# tinyduino-driver.net
KiCad netlist of a schematic drawn in EAGLE
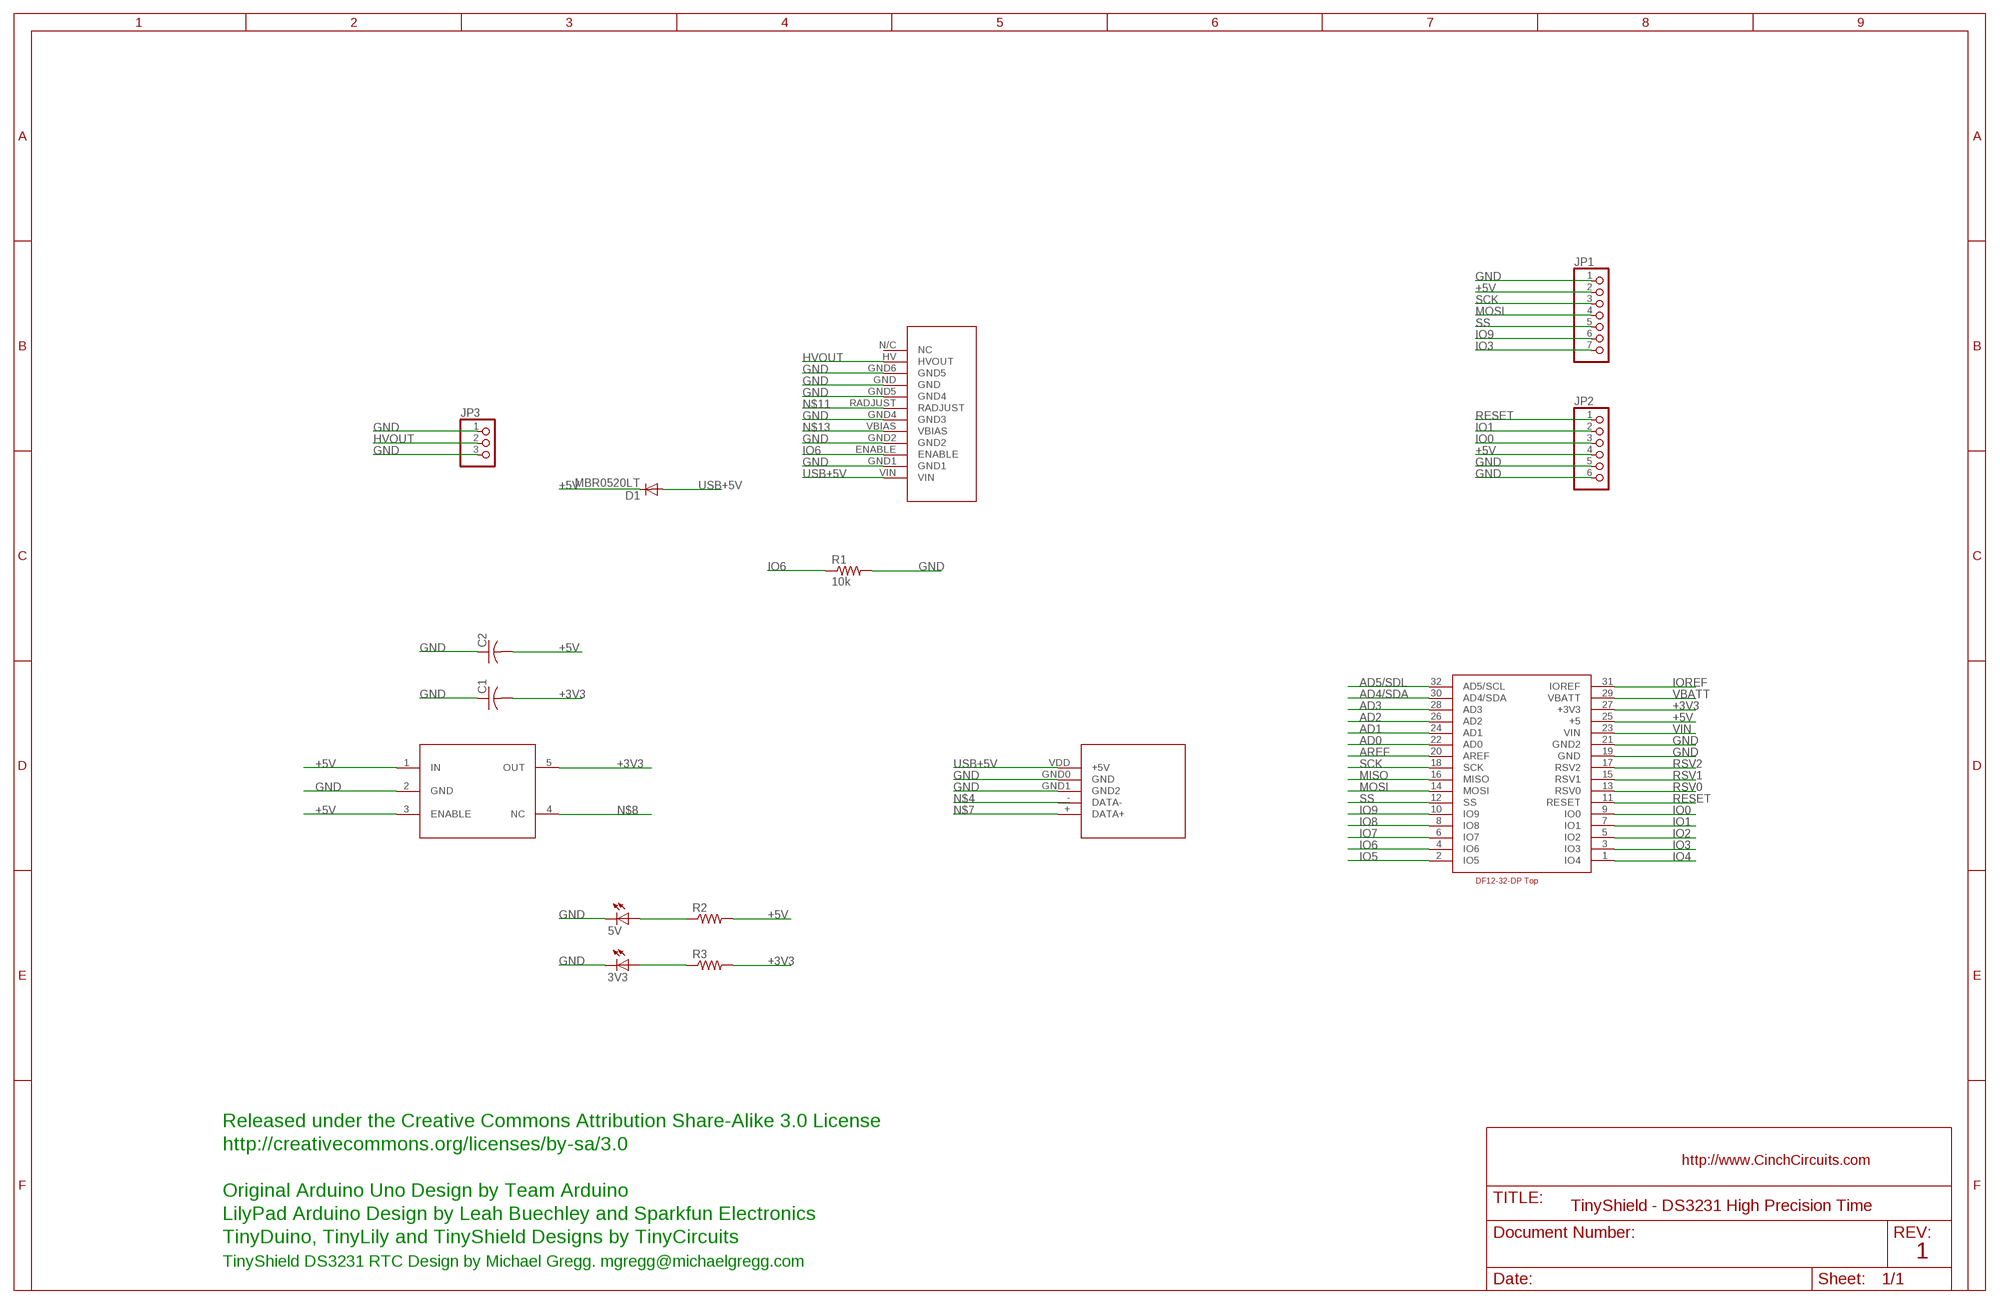
[diagram p0: schematic, sheet 1]

(export (version "E")
  (design (tool "Eeschema 10.0.6"))
  (components
    (comp (ref "3V3")
      (value "LEDCHIPLED_0603")
      (footprint "eagle-import:CHIPLED_0603")
      (libsource (lib "eagle-import") (part "LEDCHIPLED_0603"))
    )
    (comp (ref "5V")
      (value "LEDCHIPLED_0603")
      (footprint "eagle-import:CHIPLED_0603")
      (libsource (lib "eagle-import") (part "LEDCHIPLED_0603"))
    )
    (comp (ref "C1")
      (value "C-USC0805")
      (footprint "eagle-import:C0805")
      (libsource (lib "eagle-import") (part "C-USC0805"))
    )
    (comp (ref "C2")
      (value "C-USC0805")
      (footprint "eagle-import:C0805")
      (libsource (lib "eagle-import") (part "C-USC0805"))
    )
    (comp (ref "D1")
      (value "MBR0520LT")
      (footprint "eagle-import:SOD123")
      (libsource (lib "eagle-import") (part "MBR0520LT"))
    )
    (comp (ref "JP1")
      (value "PINHD-1X7")
      (footprint "eagle-import:1X07")
      (libsource (lib "eagle-import") (part "PINHD-1X7"))
    )
    (comp (ref "JP2")
      (value "PINHD-1X6")
      (footprint "eagle-import:1X06")
      (libsource (lib "eagle-import") (part "PINHD-1X6"))
    )
    (comp (ref "JP3")
      (value "PINHD-1X3")
      (footprint "eagle-import:1X03")
      (libsource (lib "eagle-import") (part "PINHD-1X3"))
    )
    (comp (ref "R1")
      (value "10k")
      (footprint "eagle-import:R0805")
      (libsource (lib "eagle-import") (part "R-US_R0805"))
    )
    (comp (ref "R2")
      (value "R-US_R0805")
      (footprint "eagle-import:R0805")
      (libsource (lib "eagle-import") (part "R-US_R0805"))
    )
    (comp (ref "R3")
      (value "R-US_R0805")
      (footprint "eagle-import:R0805")
      (libsource (lib "eagle-import") (part "R-US_R0805"))
    )
    (comp (ref "U$2")
      (value "HV-MODULE-EBAY")
      (footprint "eagle-import:NIIE-HV")
      (libsource (lib "eagle-import") (part "HV-MODULE-EBAY"))
    )
    (comp (ref "U$3")
      (value "USB-MICRO-SMD")
      (footprint "eagle-import:CONNECTER_MINI_USB2")
      (libsource (lib "eagle-import") (part "USB-MICRO-SMD"))
    )
    (comp (ref "U$4")
      (value "3V3-LDO-TI")
      (footprint "eagle-import:SOT23-5")
      (libsource (lib "eagle-import") (part "3V3-LDO-TI"))
    )
    (comp (ref "U$5")
      (value "TINYCIRCUITS-DF12-32-DS-BOTTOM")
      (footprint "eagle-import:TINYCIRCUITS_DF12-32-DS")
      (libsource (lib "eagle-import") (part "TINYCIRCUITS-DF12-32-DS-BOTTOM"))
    )
  )
  (nets
    (net (code "1") (name "/+3V3") (class "Default")
      (node (ref "C1") (pin "2") (pinfunction "2_2") (pintype "passive"))
      (node (ref "R3") (pin "2") (pinfunction "2_2") (pintype "passive"))
      (node (ref "U$4") (pin "5") (pinfunction "OUT_5") (pintype "bidirectional"))
      (node (ref "U$5") (pin "27") (pinfunction "+3V3_27") (pintype "bidirectional"))
    )
    (net (code "2") (name "/+5V") (class "Default")
      (node (ref "C2") (pin "2") (pinfunction "2_2") (pintype "passive"))
      (node (ref "D1") (pin "C") (pinfunction "C_C") (pintype "passive"))
      (node (ref "JP1") (pin "2") (pinfunction "2_2") (pintype "passive"))
      (node (ref "JP2") (pin "4") (pinfunction "4_4") (pintype "passive"))
      (node (ref "R2") (pin "2") (pinfunction "2_2") (pintype "passive"))
      (node (ref "U$4") (pin "1") (pinfunction "IN_1") (pintype "bidirectional"))
      (node (ref "U$4") (pin "3") (pinfunction "ENABLE_3") (pintype "bidirectional"))
      (node (ref "U$5") (pin "25") (pinfunction "+5_25") (pintype "bidirectional"))
    )
    (net (code "3") (name "/AD0") (class "Default")
      (node (ref "U$5") (pin "22") (pinfunction "AD0_22") (pintype "bidirectional"))
    )
    (net (code "4") (name "/AD1") (class "Default")
      (node (ref "U$5") (pin "24") (pinfunction "AD1_24") (pintype "bidirectional"))
    )
    (net (code "5") (name "/AD2") (class "Default")
      (node (ref "U$5") (pin "26") (pinfunction "AD2_26") (pintype "bidirectional"))
    )
    (net (code "6") (name "/AD3") (class "Default")
      (node (ref "U$5") (pin "28") (pinfunction "AD3_28") (pintype "bidirectional"))
    )
    (net (code "7") (name "/AD4{slash}SDA") (class "Default")
      (node (ref "U$5") (pin "30") (pinfunction "AD4/SDA_30") (pintype "bidirectional"))
    )
    (net (code "8") (name "/AD5{slash}SDL") (class "Default")
      (node (ref "U$5") (pin "32") (pinfunction "AD5/SCL_32") (pintype "bidirectional"))
    )
    (net (code "9") (name "/AREF") (class "Default")
      (node (ref "U$5") (pin "20") (pinfunction "AREF_20") (pintype "bidirectional"))
    )
    (net (code "10") (name "/GND") (class "Default")
      (node (ref "3V3") (pin "C") (pinfunction "C_C") (pintype "passive"))
      (node (ref "5V") (pin "C") (pinfunction "C_C") (pintype "passive"))
      (node (ref "C1") (pin "1") (pinfunction "1_1") (pintype "passive"))
      (node (ref "C2") (pin "1") (pinfunction "1_1") (pintype "passive"))
      (node (ref "JP1") (pin "1") (pinfunction "1_1") (pintype "passive"))
      (node (ref "JP2") (pin "5") (pinfunction "5_5") (pintype "passive"))
      (node (ref "JP2") (pin "6") (pinfunction "6_6") (pintype "passive"))
      (node (ref "JP3") (pin "1") (pinfunction "1_1") (pintype "passive"))
      (node (ref "JP3") (pin "3") (pinfunction "3_3") (pintype "passive"))
      (node (ref "R1") (pin "2") (pinfunction "2_2") (pintype "passive"))
      (node (ref "U$2") (pin "GND") (pinfunction "GND_GND") (pintype "bidirectional"))
      (node (ref "U$2") (pin "GND1") (pinfunction "GND1_GND1") (pintype "bidirectional"))
      (node (ref "U$2") (pin "GND2") (pinfunction "GND2_GND2") (pintype "bidirectional"))
      (node (ref "U$2") (pin "GND4") (pinfunction "GND3_GND4") (pintype "bidirectional"))
      (node (ref "U$2") (pin "GND5") (pinfunction "GND4_GND5") (pintype "bidirectional"))
      (node (ref "U$2") (pin "GND6") (pinfunction "GND5_GND6") (pintype "bidirectional"))
      (node (ref "U$3") (pin "GND0") (pinfunction "GND_GND0") (pintype "bidirectional"))
      (node (ref "U$3") (pin "GND1") (pinfunction "GND2_GND1") (pintype "bidirectional"))
      (node (ref "U$4") (pin "2") (pinfunction "GND_2") (pintype "bidirectional"))
      (node (ref "U$5") (pin "19") (pinfunction "GND_19") (pintype "bidirectional"))
      (node (ref "U$5") (pin "21") (pinfunction "GND2_21") (pintype "bidirectional"))
    )
    (net (code "11") (name "/HVOUT") (class "Default")
      (node (ref "JP3") (pin "2") (pinfunction "2_2") (pintype "passive"))
      (node (ref "U$2") (pin "HV") (pinfunction "HVOUT_HV") (pintype "bidirectional"))
    )
    (net (code "12") (name "/IO0") (class "Default")
      (node (ref "JP2") (pin "3") (pinfunction "3_3") (pintype "passive"))
      (node (ref "U$5") (pin "9") (pinfunction "IO0_9") (pintype "bidirectional"))
    )
    (net (code "13") (name "/IO1") (class "Default")
      (node (ref "JP2") (pin "2") (pinfunction "2_2") (pintype "passive"))
      (node (ref "U$5") (pin "7") (pinfunction "IO1_7") (pintype "bidirectional"))
    )
    (net (code "14") (name "/IO2") (class "Default")
      (node (ref "U$5") (pin "5") (pinfunction "IO2_5") (pintype "bidirectional"))
    )
    (net (code "15") (name "/IO3") (class "Default")
      (node (ref "JP1") (pin "7") (pinfunction "7_7") (pintype "passive"))
      (node (ref "U$5") (pin "3") (pinfunction "IO3_3") (pintype "bidirectional"))
    )
    (net (code "16") (name "/IO4") (class "Default")
      (node (ref "U$5") (pin "1") (pinfunction "IO4_1") (pintype "bidirectional"))
    )
    (net (code "17") (name "/IO5") (class "Default")
      (node (ref "U$5") (pin "2") (pinfunction "IO5_2") (pintype "bidirectional"))
    )
    (net (code "18") (name "/IO6") (class "Default")
      (node (ref "R1") (pin "1") (pinfunction "1_1") (pintype "passive"))
      (node (ref "U$2") (pin "ENABLE") (pinfunction "ENABLE_ENABLE") (pintype "bidirectional"))
      (node (ref "U$5") (pin "4") (pinfunction "IO6_4") (pintype "bidirectional"))
    )
    (net (code "19") (name "/IO7") (class "Default")
      (node (ref "U$5") (pin "6") (pinfunction "IO7_6") (pintype "bidirectional"))
    )
    (net (code "20") (name "/IO8") (class "Default")
      (node (ref "U$5") (pin "8") (pinfunction "IO8_8") (pintype "bidirectional"))
    )
    (net (code "21") (name "/IO9") (class "Default")
      (node (ref "JP1") (pin "6") (pinfunction "6_6") (pintype "passive"))
      (node (ref "U$5") (pin "10") (pinfunction "IO9_10") (pintype "bidirectional"))
    )
    (net (code "22") (name "/IOREF") (class "Default")
      (node (ref "U$5") (pin "31") (pinfunction "IOREF_31") (pintype "bidirectional"))
    )
    (net (code "23") (name "/MISO") (class "Default")
      (node (ref "U$5") (pin "16") (pinfunction "MISO_16") (pintype "bidirectional"))
    )
    (net (code "24") (name "/MOSI") (class "Default")
      (node (ref "JP1") (pin "4") (pinfunction "4_4") (pintype "passive"))
      (node (ref "U$5") (pin "14") (pinfunction "MOSI_14") (pintype "bidirectional"))
    )
    (net (code "26") (name "/N$7") (class "Default")
      (node (ref "U$3") (pin "+") (pinfunction "DATA+_+") (pintype "bidirectional"))
    )
    (net (code "27") (name "/N$8") (class "Default")
      (node (ref "U$4") (pin "4") (pinfunction "NC_4") (pintype "bidirectional"))
    )
    (net (code "28") (name "/N$11") (class "Default")
      (node (ref "U$2") (pin "RADJUST") (pinfunction "RADJUST_RADJUST") (pintype "bidirectional"))
    )
    (net (code "29") (name "/N$13") (class "Default")
      (node (ref "U$2") (pin "VBIAS") (pinfunction "VBIAS_VBIAS") (pintype "bidirectional"))
    )
    (net (code "30") (name "/RESET") (class "Default")
      (node (ref "JP2") (pin "1") (pinfunction "1_1") (pintype "passive"))
      (node (ref "U$5") (pin "11") (pinfunction "RESET_11") (pintype "bidirectional"))
    )
    (net (code "31") (name "/RSV0") (class "Default")
      (node (ref "U$5") (pin "13") (pinfunction "RSV0_13") (pintype "bidirectional"))
    )
    (net (code "32") (name "/RSV1") (class "Default")
      (node (ref "U$5") (pin "15") (pinfunction "RSV1_15") (pintype "bidirectional"))
    )
    (net (code "33") (name "/RSV2") (class "Default")
      (node (ref "U$5") (pin "17") (pinfunction "RSV2_17") (pintype "bidirectional"))
    )
    (net (code "34") (name "/SCK") (class "Default")
      (node (ref "JP1") (pin "3") (pinfunction "3_3") (pintype "passive"))
      (node (ref "U$5") (pin "18") (pinfunction "SCK_18") (pintype "bidirectional"))
    )
    (net (code "35") (name "/SS") (class "Default")
      (node (ref "JP1") (pin "5") (pinfunction "5_5") (pintype "passive"))
      (node (ref "U$5") (pin "12") (pinfunction "SS_12") (pintype "bidirectional"))
    )
    (net (code "36") (name "/USB+5V") (class "Default")
      (node (ref "D1") (pin "A") (pinfunction "A_A") (pintype "passive"))
      (node (ref "U$2") (pin "VIN") (pinfunction "VIN_VIN") (pintype "bidirectional"))
      (node (ref "U$3") (pin "VDD") (pinfunction "+5V_VDD") (pintype "bidirectional"))
    )
    (net (code "37") (name "/VBATT") (class "Default")
      (node (ref "U$5") (pin "29") (pinfunction "VBATT_29") (pintype "bidirectional"))
    )
    (net (code "38") (name "/VIN") (class "Default")
      (node (ref "U$5") (pin "23") (pinfunction "VIN_23") (pintype "bidirectional"))
    )
    (net (code "39") (name "Net-(3V3-PadA)") (class "Default")
      (node (ref "3V3") (pin "A") (pinfunction "A_A") (pintype "passive"))
      (node (ref "R3") (pin "1") (pinfunction "1_1") (pintype "passive"))
    )
    (net (code "40") (name "Net-(5V-PadA)") (class "Default")
      (node (ref "5V") (pin "A") (pinfunction "A_A") (pintype "passive"))
      (node (ref "R2") (pin "1") (pinfunction "1_1") (pintype "passive"))
    )
    (net (code "41") (name "unconnected-(U$2-NC-PadN{slash}C)") (class "Default")
      (node (ref "U$2") (pin "N/C") (pinfunction "NC_N/C") (pintype "bidirectional"))
    )
    (net (code "42") (name "unconnected-(U$3-DATA--Pad-)") (class "Default")
      (node (ref "U$3") (pin "-") (pinfunction "DATA-_-") (pintype "bidirectional"))
    )
  )
)
